# design.net
KiCad netlist of a schematic drawn in Altium Designer
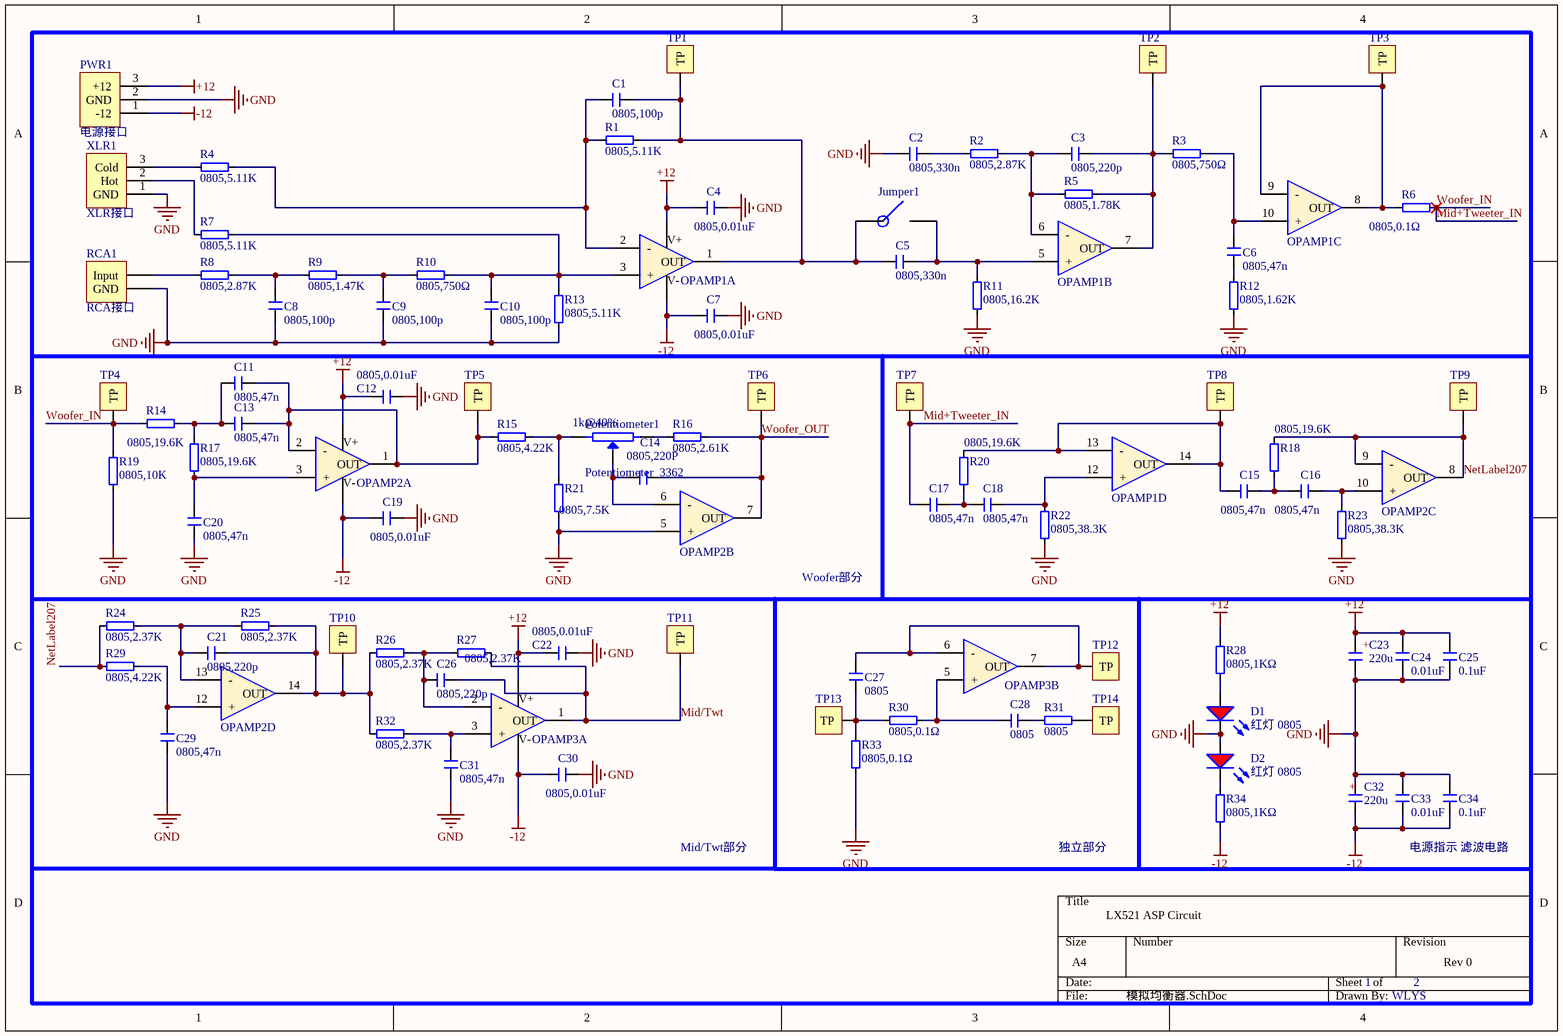
[diagram p0: 模拟均衡器.SchDoc]

(export (version "E")
  (design (tool "Eeschema 10.0.6"))
  (components
    (comp (ref "C1") (value "0805,100p") (footprint "0805_C") (libsource (lib "模拟均衡器") (part "C0805")))
    (comp (ref "C2") (value "0805,330n") (footprint "0805_C") (libsource (lib "模拟均衡器") (part "C0805")))
    (comp (ref "C3") (value "0805,220p") (footprint "0805_C") (libsource (lib "模拟均衡器") (part "C0805")))
    (comp (ref "C4")
      (value "0805,0.01uF")
      (footprint "0805_C")
      (description "0.01uF")
      (libsource (lib "模拟均衡器") (part "C0805"))
    )
    (comp (ref "C5") (value "0805,330n") (footprint "0805_C") (libsource (lib "模拟均衡器") (part "C0805")))
    (comp (ref "C6") (value "0805,47n") (footprint "0805_C") (libsource (lib "模拟均衡器") (part "C0805")))
    (comp (ref "C7")
      (value "0805,0.01uF")
      (footprint "0805_C")
      (description "0.01uF")
      (libsource (lib "模拟均衡器") (part "C0805"))
    )
    (comp (ref "C8") (value "0805,100p") (footprint "0805_C") (libsource (lib "模拟均衡器") (part "C0805")))
    (comp (ref "C9") (value "0805,100p") (footprint "0805_C") (libsource (lib "模拟均衡器") (part "C0805")))
    (comp (ref "C10") (value "0805,100p") (footprint "0805_C") (libsource (lib "模拟均衡器") (part "C0805")))
    (comp (ref "C11") (value "0805,47n") (footprint "0805_C") (libsource (lib "模拟均衡器") (part "C0805")))
    (comp (ref "C12")
      (value "0805,0.01uF")
      (footprint "0805_C")
      (description "0.01uF")
      (libsource (lib "模拟均衡器") (part "C0805"))
    )
    (comp (ref "C13") (value "0805,47n") (footprint "0805_C") (libsource (lib "模拟均衡器") (part "C0805")))
    (comp (ref "C14") (value "0805,220P") (footprint "0805_C") (libsource (lib "模拟均衡器") (part "C0805")))
    (comp (ref "C15") (value "0805,47n") (footprint "0805_C") (libsource (lib "模拟均衡器") (part "C0805")))
    (comp (ref "C16") (value "0805,47n") (footprint "0805_C") (libsource (lib "模拟均衡器") (part "C0805")))
    (comp (ref "C17") (value "0805,47n") (footprint "0805_C") (libsource (lib "模拟均衡器") (part "C0805")))
    (comp (ref "C18") (value "0805,47n") (footprint "0805_C") (libsource (lib "模拟均衡器") (part "C0805")))
    (comp (ref "C19")
      (value "0805,0.01uF")
      (footprint "0805_C")
      (description "0.01uF")
      (libsource (lib "模拟均衡器") (part "C0805"))
    )
    (comp (ref "C20") (value "0805,47n") (footprint "0805_C") (libsource (lib "模拟均衡器") (part "C0805")))
    (comp (ref "C21") (value "0805,220p") (footprint "0805_C") (libsource (lib "模拟均衡器") (part "C0805")))
    (comp (ref "C22")
      (value "0805,0.01uF")
      (footprint "0805_C")
      (description "0.01uF")
      (libsource (lib "模拟均衡器") (part "C0805"))
    )
    (comp (ref "C23") (value "220u") (libsource (lib "模拟均衡器") (part "C直插电解")))
    (comp (ref "C24") (value "0.01uF") (footprint "0805_C") (libsource (lib "模拟均衡器") (part "C0805")))
    (comp (ref "C25") (value "0.1uF") (footprint "0805_C") (libsource (lib "模拟均衡器") (part "C0805")))
    (comp (ref "C26") (value "0805,220p") (footprint "0805_C") (libsource (lib "模拟均衡器") (part "C0805")))
    (comp (ref "C27")
      (value "0805")
      (footprint "0805_C")
      (description "0.01uF")
      (libsource (lib "模拟均衡器") (part "C0805"))
    )
    (comp (ref "C28")
      (value "0805")
      (footprint "0805_C")
      (description "0.01uF")
      (libsource (lib "模拟均衡器") (part "C0805"))
    )
    (comp (ref "C29") (value "0805,47n") (footprint "0805_C") (libsource (lib "模拟均衡器") (part "C0805")))
    (comp (ref "C30")
      (value "0805,0.01uF")
      (footprint "0805_C")
      (description "0.01uF")
      (libsource (lib "模拟均衡器") (part "C0805"))
    )
    (comp (ref "C31") (value "0805,47n") (footprint "0805_C") (libsource (lib "模拟均衡器") (part "C0805")))
    (comp (ref "C32") (value "220u") (libsource (lib "模拟均衡器") (part "C直插电解")))
    (comp (ref "C33") (value "0.01uF") (footprint "0805_C") (libsource (lib "模拟均衡器") (part "C0805")))
    (comp (ref "C34") (value "0.1uF") (footprint "0805_C") (libsource (lib "模拟均衡器") (part "C0805")))
    (comp (ref "D1")
      (value "红灯 0805")
      (footprint "0805_LED_S3")
      (description "发光二极管")
      (libsource (lib "模拟均衡器") (part "0805 红灯"))
    )
    (comp (ref "D2")
      (value "红灯 0805")
      (footprint "0805_LED_S3")
      (description "发光二极管")
      (libsource (lib "模拟均衡器") (part "0805 红灯"))
    )
    (comp (ref "Jumper1") (value "Jumper") (footprint "0805_J") (libsource (lib "模拟均衡器") (part "Jumper")))
    (comp (ref "OPAMP1")
      (value "4277UA")
      (footprint "SOIC-14_150mil")
      (libsource (lib "模拟均衡器") (part "OPA4277UA"))
    )
    (comp (ref "OPAMP2")
      (value "4277UA")
      (footprint "SOIC-14_150mil")
      (libsource (lib "模拟均衡器") (part "OPA4277UA"))
    )
    (comp (ref "OPAMP3")
      (value "4277UA")
      (footprint "SOIC-14_150mil")
      (libsource (lib "模拟均衡器") (part "OPA4277UA"))
    )
    (comp (ref "Potentiometer1")
      (value "Potentiometer_3362")
      (footprint "3362P")
      (libsource (lib "模拟均衡器") (part "Potentiometer_3362"))
    )
    (comp (ref "PWR1") (value "电源接口") (libsource (lib "模拟均衡器") (part "电源接口")))
    (comp (ref "R1") (value "0805,5.11K") (footprint "0805_R") (libsource (lib "模拟均衡器") (part "R0805")))
    (comp (ref "R2") (value "0805,2.87K") (footprint "0805_R") (libsource (lib "模拟均衡器") (part "R0805")))
    (comp (ref "R3") (value "0805,750Ω") (footprint "0805_R") (libsource (lib "模拟均衡器") (part "R0805")))
    (comp (ref "R4") (value "0805,5.11K") (footprint "0805_R") (libsource (lib "模拟均衡器") (part "R0805")))
    (comp (ref "R5") (value "0805,1.78K") (footprint "0805_R") (libsource (lib "模拟均衡器") (part "R0805")))
    (comp (ref "R6") (value "0805,0.1Ω") (footprint "0805_R") (libsource (lib "模拟均衡器") (part "R0805")))
    (comp (ref "R7") (value "0805,5.11K") (footprint "0805_R") (libsource (lib "模拟均衡器") (part "R0805")))
    (comp (ref "R8") (value "0805,2.87K") (footprint "0805_R") (libsource (lib "模拟均衡器") (part "R0805")))
    (comp (ref "R9") (value "0805,1.47K") (footprint "0805_R") (libsource (lib "模拟均衡器") (part "R0805")))
    (comp (ref "R10") (value "0805,750Ω") (footprint "0805_R") (libsource (lib "模拟均衡器") (part "R0805")))
    (comp (ref "R11") (value "0805,16.2K") (footprint "0805_R") (libsource (lib "模拟均衡器") (part "R0805")))
    (comp (ref "R12") (value "0805,1.62K") (footprint "0805_R") (libsource (lib "模拟均衡器") (part "R0805")))
    (comp (ref "R13") (value "0805,5.11K") (footprint "0805_R") (libsource (lib "模拟均衡器") (part "R0805")))
    (comp (ref "R14") (value "0805,19.6K") (footprint "0805_R") (libsource (lib "模拟均衡器") (part "R0805")))
    (comp (ref "R15") (value "0805,4.22K") (footprint "0805_R") (libsource (lib "模拟均衡器") (part "R0805")))
    (comp (ref "R16") (value "0805,2.61K") (footprint "0805_R") (libsource (lib "模拟均衡器") (part "R0805")))
    (comp (ref "R17") (value "0805,19.6K") (footprint "0805_R") (libsource (lib "模拟均衡器") (part "R0805")))
    (comp (ref "R18") (value "0805,19.6K") (footprint "0805_R") (libsource (lib "模拟均衡器") (part "R0805")))
    (comp (ref "R19") (value "0805,10K") (footprint "0805_R") (libsource (lib "模拟均衡器") (part "R0805")))
    (comp (ref "R20") (value "0805,19.6K") (footprint "0805_R") (libsource (lib "模拟均衡器") (part "R0805")))
    (comp (ref "R21") (value "0805,7.5K") (footprint "0805_R") (libsource (lib "模拟均衡器") (part "R0805")))
    (comp (ref "R22") (value "0805,38.3K") (footprint "0805_R") (libsource (lib "模拟均衡器") (part "R0805")))
    (comp (ref "R23") (value "0805,38.3K") (footprint "0805_R") (libsource (lib "模拟均衡器") (part "R0805")))
    (comp (ref "R24") (value "0805,2.37K") (footprint "0805_R") (libsource (lib "模拟均衡器") (part "R0805")))
    (comp (ref "R25") (value "0805,2.37K") (footprint "0805_R") (libsource (lib "模拟均衡器") (part "R0805")))
    (comp (ref "R26") (value "0805,2.37K") (footprint "0805_R") (libsource (lib "模拟均衡器") (part "R0805")))
    (comp (ref "R27") (value "0805,2.37K") (footprint "0805_R") (libsource (lib "模拟均衡器") (part "R0805")))
    (comp (ref "R28") (value "0805,1KΩ") (footprint "0805_R") (libsource (lib "模拟均衡器") (part "R0805")))
    (comp (ref "R29") (value "0805,4.22K") (footprint "0805_R") (libsource (lib "模拟均衡器") (part "R0805")))
    (comp (ref "R30") (value "0805,0.1Ω") (footprint "0805_R") (libsource (lib "模拟均衡器") (part "R0805")))
    (comp (ref "R31") (value "0805") (footprint "0805_R") (libsource (lib "模拟均衡器") (part "R0805")))
    (comp (ref "R32") (value "0805,2.37K") (footprint "0805_R") (libsource (lib "模拟均衡器") (part "R0805")))
    (comp (ref "R33") (value "0805,0.1Ω") (footprint "0805_R") (libsource (lib "模拟均衡器") (part "R0805")))
    (comp (ref "R34") (value "0805,1KΩ") (footprint "0805_R") (libsource (lib "模拟均衡器") (part "R0805")))
    (comp (ref "RCA1") (value "RCA接口") (footprint "XH2.54-LI-2P") (libsource (lib "模拟均衡器") (part "RCA接口")))
    (comp (ref "TP1") (value "测试点") (footprint "TestPoint") (libsource (lib "模拟均衡器") (part "测试点")))
    (comp (ref "TP2") (value "测试点") (footprint "TestPoint") (libsource (lib "模拟均衡器") (part "测试点")))
    (comp (ref "TP3") (value "测试点") (footprint "TestPoint") (libsource (lib "模拟均衡器") (part "测试点")))
    (comp (ref "TP4") (value "测试点") (footprint "TestPoint") (libsource (lib "模拟均衡器") (part "测试点")))
    (comp (ref "TP5") (value "测试点") (footprint "TestPoint") (libsource (lib "模拟均衡器") (part "测试点")))
    (comp (ref "TP6") (value "测试点") (footprint "TestPoint") (libsource (lib "模拟均衡器") (part "测试点")))
    (comp (ref "TP7") (value "测试点") (footprint "TestPoint") (libsource (lib "模拟均衡器") (part "测试点")))
    (comp (ref "TP8") (value "测试点") (footprint "TestPoint") (libsource (lib "模拟均衡器") (part "测试点")))
    (comp (ref "TP9") (value "测试点") (footprint "TestPoint") (libsource (lib "模拟均衡器") (part "测试点")))
    (comp (ref "TP10") (value "测试点") (footprint "TestPoint") (libsource (lib "模拟均衡器") (part "测试点")))
    (comp (ref "TP11") (value "测试点") (footprint "TestPoint") (libsource (lib "模拟均衡器") (part "测试点")))
    (comp (ref "TP12") (value "测试点") (footprint "TestPoint") (libsource (lib "") (part "测试点_2")))
    (comp (ref "TP13") (value "测试点") (footprint "TestPoint") (libsource (lib "") (part "测试点_1")))
    (comp (ref "TP14") (value "测试点") (footprint "TestPoint") (libsource (lib "") (part "测试点_2")))
    (comp (ref "XLR1") (value "XLR接口") (libsource (lib "模拟均衡器") (part "XLR接口")))
  )
  (nets
    (net (code "1") (name "+12") (class "Default")
      (node (ref "C12") (pin "1") (pinfunction "1_1") (pintype "passive"))
      (node (ref "C22") (pin "1") (pinfunction "1_1") (pintype "passive"))
      (node (ref "C23") (pin "1") (pinfunction "1_1") (pintype "passive"))
      (node (ref "C24") (pin "2") (pinfunction "2_2") (pintype "passive"))
      (node (ref "C25") (pin "2") (pinfunction "2_2") (pintype "passive"))
      (node (ref "C4") (pin "1") (pinfunction "1_1") (pintype "passive"))
      (node (ref "OPAMP1") (pin "4") (pinfunction "V+_4") (pintype "passive"))
      (node (ref "OPAMP2") (pin "4") (pinfunction "V+_4") (pintype "passive"))
      (node (ref "OPAMP3") (pin "4") (pinfunction "V+_4") (pintype "passive"))
      (node (ref "PWR1") (pin "3") (pinfunction "+12_3") (pintype "passive"))
      (node (ref "R28") (pin "1") (pinfunction "1_1") (pintype "passive"))
    )
    (net (code "2") (name "-12") (class "Default")
      (node (ref "C19") (pin "1") (pinfunction "1_1") (pintype "passive"))
      (node (ref "C30") (pin "1") (pinfunction "1_1") (pintype "passive"))
      (node (ref "C32") (pin "2") (pinfunction "2_2") (pintype "passive"))
      (node (ref "C33") (pin "1") (pinfunction "1_1") (pintype "passive"))
      (node (ref "C34") (pin "1") (pinfunction "1_1") (pintype "passive"))
      (node (ref "C7") (pin "1") (pinfunction "1_1") (pintype "passive"))
      (node (ref "OPAMP1") (pin "11") (pinfunction "V-_11") (pintype "passive"))
      (node (ref "OPAMP2") (pin "11") (pinfunction "V-_11") (pintype "passive"))
      (node (ref "OPAMP3") (pin "11") (pinfunction "V-_11") (pintype "passive"))
      (node (ref "PWR1") (pin "1") (pinfunction "-12_1") (pintype "passive"))
      (node (ref "R34") (pin "2") (pinfunction "2_2") (pintype "passive"))
    )
    (net (code "3") (name "/Mid+Tweeter_IN") (class "Default")
      (node (ref "C17") (pin "1") (pinfunction "1_1") (pintype "passive"))
      (node (ref "R14") (pin "1") (pinfunction "1_1") (pintype "passive"))
      (node (ref "R19") (pin "2") (pinfunction "2_2") (pintype "passive"))
      (node (ref "R6") (pin "2") (pinfunction "2_2") (pintype "passive"))
      (node (ref "TP4") (pin "1") (pinfunction "TP_1") (pintype "passive"))
      (node (ref "TP7") (pin "1") (pinfunction "TP_1") (pintype "passive"))
    )
    (net (code "4") (name "/Mid{slash}Twt") (class "Default")
      (node (ref "C26") (pin "1") (pinfunction "1_1") (pintype "passive"))
      (node (ref "OPAMP3") (pin "1") (pinfunction "OUT_1") (pintype "passive"))
      (node (ref "R27") (pin "1") (pinfunction "1_1") (pintype "passive"))
      (node (ref "TP11") (pin "1") (pinfunction "TP_1") (pintype "passive"))
    )
    (net (code "5") (name "/NetLabel207") (class "Default")
      (node (ref "OPAMP2") (pin "8") (pinfunction "OUT_8") (pintype "passive"))
      (node (ref "OPAMP2") (pin "9") (pinfunction "-_9") (pintype "passive"))
      (node (ref "R18") (pin "2") (pinfunction "2_2") (pintype "passive"))
      (node (ref "R24") (pin "2") (pinfunction "2_2") (pintype "passive"))
      (node (ref "R29") (pin "2") (pinfunction "2_2") (pintype "passive"))
      (node (ref "TP9") (pin "1") (pinfunction "TP_1") (pintype "passive"))
    )
    (net (code "6") (name "/Woofer_OUT") (class "Default")
      (node (ref "C14") (pin "1") (pinfunction "1_1") (pintype "passive"))
      (node (ref "OPAMP2") (pin "7") (pinfunction "OUT_7") (pintype "passive"))
      (node (ref "R16") (pin "1") (pinfunction "1_1") (pintype "passive"))
      (node (ref "TP6") (pin "1") (pinfunction "TP_1") (pintype "passive"))
    )
    (net (code "7") (name "GND") (class "Default")
      (node (ref "C10") (pin "2") (pinfunction "2_2") (pintype "passive"))
      (node (ref "C12") (pin "2") (pinfunction "2_2") (pintype "passive"))
      (node (ref "C19") (pin "2") (pinfunction "2_2") (pintype "passive"))
      (node (ref "C2") (pin "1") (pinfunction "1_1") (pintype "passive"))
      (node (ref "C20") (pin "1") (pinfunction "1_1") (pintype "passive"))
      (node (ref "C22") (pin "2") (pinfunction "2_2") (pintype "passive"))
      (node (ref "C23") (pin "2") (pinfunction "2_2") (pintype "passive"))
      (node (ref "C24") (pin "1") (pinfunction "1_1") (pintype "passive"))
      (node (ref "C25") (pin "1") (pinfunction "1_1") (pintype "passive"))
      (node (ref "C29") (pin "1") (pinfunction "1_1") (pintype "passive"))
      (node (ref "C30") (pin "2") (pinfunction "2_2") (pintype "passive"))
      (node (ref "C31") (pin "1") (pinfunction "1_1") (pintype "passive"))
      (node (ref "C32") (pin "1") (pinfunction "1_1") (pintype "passive"))
      (node (ref "C33") (pin "2") (pinfunction "2_2") (pintype "passive"))
      (node (ref "C34") (pin "2") (pinfunction "2_2") (pintype "passive"))
      (node (ref "C4") (pin "2") (pinfunction "2_2") (pintype "passive"))
      (node (ref "C7") (pin "2") (pinfunction "2_2") (pintype "passive"))
      (node (ref "C8") (pin "2") (pinfunction "2_2") (pintype "passive"))
      (node (ref "C9") (pin "2") (pinfunction "2_2") (pintype "passive"))
      (node (ref "D1") (pin "K") (pinfunction "K_K") (pintype "passive"))
      (node (ref "D2") (pin "A") (pinfunction "A_A") (pintype "passive"))
      (node (ref "OPAMP2") (pin "5") (pinfunction "+_5") (pintype "passive"))
      (node (ref "PWR1") (pin "2") (pinfunction "GND_2") (pintype "passive"))
      (node (ref "R11") (pin "1") (pinfunction "1_1") (pintype "passive"))
      (node (ref "R12") (pin "1") (pinfunction "1_1") (pintype "passive"))
      (node (ref "R13") (pin "1") (pinfunction "1_1") (pintype "passive"))
      (node (ref "R19") (pin "1") (pinfunction "1_1") (pintype "passive"))
      (node (ref "R21") (pin "2") (pinfunction "2_2") (pintype "passive"))
      (node (ref "R22") (pin "1") (pinfunction "1_1") (pintype "passive"))
      (node (ref "R23") (pin "1") (pinfunction "1_1") (pintype "passive"))
      (node (ref "R33") (pin "2") (pinfunction "2_2") (pintype "passive"))
      (node (ref "RCA1") (pin "2") (pinfunction "GND_2") (pintype "passive"))
      (node (ref "XLR1") (pin "1") (pinfunction "GND_1") (pintype "passive"))
    )
    (net (code "8") (name "Net-(C2-Pad2)") (class "Default")
      (node (ref "C2") (pin "2") (pinfunction "2_2") (pintype "passive"))
      (node (ref "R2") (pin "1") (pinfunction "1_1") (pintype "passive"))
    )
    (net (code "9") (name "Net-(C6-Pad1)") (class "Default")
      (node (ref "C6") (pin "1") (pinfunction "1_1") (pintype "passive"))
      (node (ref "R12") (pin "2") (pinfunction "2_2") (pintype "passive"))
    )
    (net (code "10") (name "Net-(C8-Pad1)") (class "Default")
      (node (ref "C8") (pin "1") (pinfunction "1_1") (pintype "passive"))
      (node (ref "R8") (pin "2") (pinfunction "2_2") (pintype "passive"))
      (node (ref "R9") (pin "1") (pinfunction "1_1") (pintype "passive"))
    )
    (net (code "11") (name "Net-(C9-Pad1)") (class "Default")
      (node (ref "C9") (pin "1") (pinfunction "1_1") (pintype "passive"))
      (node (ref "R10") (pin "1") (pinfunction "1_1") (pintype "passive"))
      (node (ref "R9") (pin "2") (pinfunction "2_2") (pintype "passive"))
    )
    (net (code "12") (name "Net-(C11-Pad2)") (class "Default")
      (node (ref "C11") (pin "2") (pinfunction "2_2") (pintype "passive"))
      (node (ref "C13") (pin "2") (pinfunction "2_2") (pintype "passive"))
      (node (ref "R14") (pin "2") (pinfunction "2_2") (pintype "passive"))
      (node (ref "R17") (pin "2") (pinfunction "2_2") (pintype "passive"))
    )
    (net (code "13") (name "Net-(C15-Pad1)") (class "Default")
      (node (ref "C15") (pin "1") (pinfunction "1_1") (pintype "passive"))
      (node (ref "C16") (pin "2") (pinfunction "2_2") (pintype "passive"))
      (node (ref "R18") (pin "1") (pinfunction "1_1") (pintype "passive"))
    )
    (net (code "14") (name "Net-(C17-Pad2)") (class "Default")
      (node (ref "C17") (pin "2") (pinfunction "2_2") (pintype "passive"))
      (node (ref "C18") (pin "1") (pinfunction "1_1") (pintype "passive"))
      (node (ref "R20") (pin "1") (pinfunction "1_1") (pintype "passive"))
    )
    (net (code "15") (name "Net-(C28-Pad1)") (class "Default")
      (node (ref "C28") (pin "1") (pinfunction "1_1") (pintype "passive"))
      (node (ref "R31") (pin "2") (pinfunction "2_2") (pintype "passive"))
    )
    (net (code "16") (name "Net-(D1-PadA)") (class "Default")
      (node (ref "D1") (pin "A") (pinfunction "A_A") (pintype "passive"))
      (node (ref "R28") (pin "2") (pinfunction "2_2") (pintype "passive"))
    )
    (net (code "17") (name "Net-(D2-PadK)") (class "Default")
      (node (ref "D2") (pin "K") (pinfunction "K_K") (pintype "passive"))
      (node (ref "R34") (pin "1") (pinfunction "1_1") (pintype "passive"))
    )
    (net (code "18") (name "Net-(OPAMP1A-+)") (class "Default")
      (node (ref "C10") (pin "1") (pinfunction "1_1") (pintype "passive"))
      (node (ref "OPAMP1") (pin "3") (pinfunction "+_3") (pintype "passive"))
      (node (ref "R10") (pin "2") (pinfunction "2_2") (pintype "passive"))
      (node (ref "R13") (pin "2") (pinfunction "2_2") (pintype "passive"))
      (node (ref "R7") (pin "2") (pinfunction "2_2") (pintype "passive"))
    )
    (net (code "19") (name "Net-(OPAMP1A--)") (class "Default")
      (node (ref "C1") (pin "1") (pinfunction "1_1") (pintype "passive"))
      (node (ref "OPAMP1") (pin "2") (pinfunction "-_2") (pintype "passive"))
      (node (ref "R1") (pin "1") (pinfunction "1_1") (pintype "passive"))
      (node (ref "R4") (pin "2") (pinfunction "2_2") (pintype "passive"))
    )
    (net (code "20") (name "Net-(OPAMP1A-OUT)") (class "Default")
      (node (ref "C1") (pin "2") (pinfunction "2_2") (pintype "passive"))
      (node (ref "C5") (pin "1") (pinfunction "1_1") (pintype "passive"))
      (node (ref "Jumper1") (pin "1") (pinfunction "1_1") (pintype "passive"))
      (node (ref "OPAMP1") (pin "1") (pinfunction "OUT_1") (pintype "passive"))
      (node (ref "R1") (pin "2") (pinfunction "2_2") (pintype "passive"))
      (node (ref "TP1") (pin "1") (pinfunction "TP_1") (pintype "passive"))
    )
    (net (code "21") (name "Net-(OPAMP1B-+)") (class "Default")
      (node (ref "C5") (pin "2") (pinfunction "2_2") (pintype "passive"))
      (node (ref "Jumper1") (pin "2") (pinfunction "2_2") (pintype "passive"))
      (node (ref "OPAMP1") (pin "5") (pinfunction "+_5") (pintype "passive"))
      (node (ref "R11") (pin "2") (pinfunction "2_2") (pintype "passive"))
    )
    (net (code "22") (name "Net-(OPAMP1B--)") (class "Default")
      (node (ref "C3") (pin "1") (pinfunction "1_1") (pintype "passive"))
      (node (ref "OPAMP1") (pin "6") (pinfunction "-_6") (pintype "passive"))
      (node (ref "R2") (pin "2") (pinfunction "2_2") (pintype "passive"))
      (node (ref "R5") (pin "1") (pinfunction "1_1") (pintype "passive"))
    )
    (net (code "23") (name "Net-(OPAMP1B-OUT)") (class "Default")
      (node (ref "C3") (pin "2") (pinfunction "2_2") (pintype "passive"))
      (node (ref "OPAMP1") (pin "7") (pinfunction "OUT_7") (pintype "passive"))
      (node (ref "R3") (pin "1") (pinfunction "1_1") (pintype "passive"))
      (node (ref "R5") (pin "2") (pinfunction "2_2") (pintype "passive"))
      (node (ref "TP2") (pin "1") (pinfunction "TP_1") (pintype "passive"))
    )
    (net (code "24") (name "Net-(OPAMP1C-+)") (class "Default")
      (node (ref "C6") (pin "2") (pinfunction "2_2") (pintype "passive"))
      (node (ref "OPAMP1") (pin "10") (pinfunction "+_10") (pintype "passive"))
      (node (ref "R3") (pin "2") (pinfunction "2_2") (pintype "passive"))
    )
    (net (code "25") (name "Net-(OPAMP1C--)") (class "Default")
      (node (ref "OPAMP1") (pin "8") (pinfunction "OUT_8") (pintype "passive"))
      (node (ref "OPAMP1") (pin "9") (pinfunction "-_9") (pintype "passive"))
      (node (ref "R6") (pin "1") (pinfunction "1_1") (pintype "passive"))
      (node (ref "TP3") (pin "1") (pinfunction "TP_1") (pintype "passive"))
    )
    (net (code "26") (name "Net-(OPAMP1D-+)") (class "Default")
      (node (ref "C18") (pin "2") (pinfunction "2_2") (pintype "passive"))
      (node (ref "OPAMP1") (pin "12") (pinfunction "+_12") (pintype "passive"))
      (node (ref "R22") (pin "2") (pinfunction "2_2") (pintype "passive"))
    )
    (net (code "27") (name "Net-(OPAMP1D--)") (class "Default")
      (node (ref "C15") (pin "2") (pinfunction "2_2") (pintype "passive"))
      (node (ref "OPAMP1") (pin "13") (pinfunction "-_13") (pintype "passive"))
      (node (ref "OPAMP1") (pin "14") (pinfunction "OUT_14") (pintype "passive"))
      (node (ref "R20") (pin "2") (pinfunction "2_2") (pintype "passive"))
      (node (ref "TP8") (pin "1") (pinfunction "TP_1") (pintype "passive"))
    )
    (net (code "28") (name "Net-(OPAMP2A-+)") (class "Default")
      (node (ref "C20") (pin "2") (pinfunction "2_2") (pintype "passive"))
      (node (ref "OPAMP2") (pin "3") (pinfunction "+_3") (pintype "passive"))
      (node (ref "R17") (pin "1") (pinfunction "1_1") (pintype "passive"))
    )
    (net (code "29") (name "Net-(OPAMP2A--)") (class "Default")
      (node (ref "C11") (pin "1") (pinfunction "1_1") (pintype "passive"))
      (node (ref "C13") (pin "1") (pinfunction "1_1") (pintype "passive"))
      (node (ref "OPAMP2") (pin "1") (pinfunction "OUT_1") (pintype "passive"))
      (node (ref "OPAMP2") (pin "2") (pinfunction "-_2") (pintype "passive"))
      (node (ref "R15") (pin "2") (pinfunction "2_2") (pintype "passive"))
      (node (ref "TP5") (pin "1") (pinfunction "TP_1") (pintype "passive"))
    )
    (net (code "30") (name "Net-(OPAMP2B--)") (class "Default")
      (node (ref "C14") (pin "2") (pinfunction "2_2") (pintype "passive"))
      (node (ref "OPAMP2") (pin "6") (pinfunction "-_6") (pintype "passive"))
      (node (ref "Potentiometer1") (pin "2") (pinfunction "W_2") (pintype "passive"))
    )
    (net (code "31") (name "Net-(OPAMP2C-+)") (class "Default")
      (node (ref "C16") (pin "1") (pinfunction "1_1") (pintype "passive"))
      (node (ref "OPAMP2") (pin "10") (pinfunction "+_10") (pintype "passive"))
      (node (ref "R23") (pin "2") (pinfunction "2_2") (pintype "passive"))
    )
    (net (code "32") (name "Net-(OPAMP2D-+)") (class "Default")
      (node (ref "C29") (pin "2") (pinfunction "2_2") (pintype "passive"))
      (node (ref "OPAMP2") (pin "12") (pinfunction "+_12") (pintype "passive"))
      (node (ref "R29") (pin "1") (pinfunction "1_1") (pintype "passive"))
    )
    (net (code "33") (name "Net-(OPAMP2D--)") (class "Default")
      (node (ref "C21") (pin "2") (pinfunction "2_2") (pintype "passive"))
      (node (ref "OPAMP2") (pin "13") (pinfunction "-_13") (pintype "passive"))
      (node (ref "R24") (pin "1") (pinfunction "1_1") (pintype "passive"))
      (node (ref "R25") (pin "2") (pinfunction "2_2") (pintype "passive"))
    )
    (net (code "34") (name "Net-(OPAMP2D-OUT)") (class "Default")
      (node (ref "C21") (pin "1") (pinfunction "1_1") (pintype "passive"))
      (node (ref "OPAMP2") (pin "14") (pinfunction "OUT_14") (pintype "passive"))
      (node (ref "R25") (pin "1") (pinfunction "1_1") (pintype "passive"))
      (node (ref "R26") (pin "2") (pinfunction "2_2") (pintype "passive"))
      (node (ref "R32") (pin "2") (pinfunction "2_2") (pintype "passive"))
      (node (ref "TP10") (pin "1") (pinfunction "TP_1") (pintype "passive"))
    )
    (net (code "35") (name "Net-(OPAMP3A-+)") (class "Default")
      (node (ref "C31") (pin "2") (pinfunction "2_2") (pintype "passive"))
      (node (ref "OPAMP3") (pin "3") (pinfunction "+_3") (pintype "passive"))
      (node (ref "R32") (pin "1") (pinfunction "1_1") (pintype "passive"))
    )
    (net (code "36") (name "Net-(OPAMP3A--)") (class "Default")
      (node (ref "C26") (pin "2") (pinfunction "2_2") (pintype "passive"))
      (node (ref "OPAMP3") (pin "2") (pinfunction "-_2") (pintype "passive"))
      (node (ref "R26") (pin "1") (pinfunction "1_1") (pintype "passive"))
      (node (ref "R27") (pin "2") (pinfunction "2_2") (pintype "passive"))
    )
    (net (code "37") (name "Net-(OPAMP3B-+)") (class "Default")
      (node (ref "C28") (pin "2") (pinfunction "2_2") (pintype "passive"))
      (node (ref "OPAMP3") (pin "5") (pinfunction "+_5") (pintype "passive"))
      (node (ref "R30") (pin "1") (pinfunction "1_1") (pintype "passive"))
    )
    (net (code "38") (name "Net-(OPAMP3B--)") (class "Default")
      (node (ref "C27") (pin "2") (pinfunction "2_2") (pintype "passive"))
      (node (ref "OPAMP3") (pin "6") (pinfunction "-_6") (pintype "passive"))
      (node (ref "OPAMP3") (pin "7") (pinfunction "OUT_7") (pintype "passive"))
      (node (ref "TP12") (pin "1") (pinfunction "TP_1") (pintype "passive"))
    )
    (net (code "39") (name "Net-(Potentiometer1-2)") (class "Default")
      (node (ref "Potentiometer1") (pin "3") (pinfunction "2_3") (pintype "passive"))
      (node (ref "R15") (pin "1") (pinfunction "1_1") (pintype "passive"))
      (node (ref "R21") (pin "1") (pinfunction "1_1") (pintype "passive"))
    )
    (net (code "40") (name "Net-(Potentiometer1-Pad1)") (class "Default")
      (node (ref "Potentiometer1") (pin "1") (pinfunction "1_1") (pintype "passive"))
      (node (ref "R16") (pin "2") (pinfunction "2_2") (pintype "passive"))
    )
    (net (code "41") (name "Net-(RCA1-Input)") (class "Default")
      (node (ref "R8") (pin "1") (pinfunction "1_1") (pintype "passive"))
      (node (ref "RCA1") (pin "1") (pinfunction "Input_1") (pintype "passive"))
    )
    (net (code "42") (name "Net-(TP13-TP)") (class "Default")
      (node (ref "C27") (pin "1") (pinfunction "1_1") (pintype "passive"))
      (node (ref "R30") (pin "2") (pinfunction "2_2") (pintype "passive"))
      (node (ref "R33") (pin "1") (pinfunction "1_1") (pintype "passive"))
      (node (ref "TP13") (pin "1") (pinfunction "TP_1") (pintype "passive"))
    )
    (net (code "43") (name "Net-(TP14-TP)") (class "Default")
      (node (ref "R31") (pin "1") (pinfunction "1_1") (pintype "passive"))
      (node (ref "TP14") (pin "1") (pinfunction "TP_1") (pintype "passive"))
    )
    (net (code "44") (name "Net-(XLR1-Cold)") (class "Default")
      (node (ref "R4") (pin "1") (pinfunction "1_1") (pintype "passive"))
      (node (ref "XLR1") (pin "3") (pinfunction "Cold_3") (pintype "passive"))
    )
    (net (code "45") (name "Net-(XLR1-Hot)") (class "Default")
      (node (ref "R7") (pin "1") (pinfunction "1_1") (pintype "passive"))
      (node (ref "XLR1") (pin "2") (pinfunction "Hot_2") (pintype "passive"))
    )
  )
)
